# Pasa_Banda_Inferior.net
KiCad netlist of a schematic drawn in Altium Designer
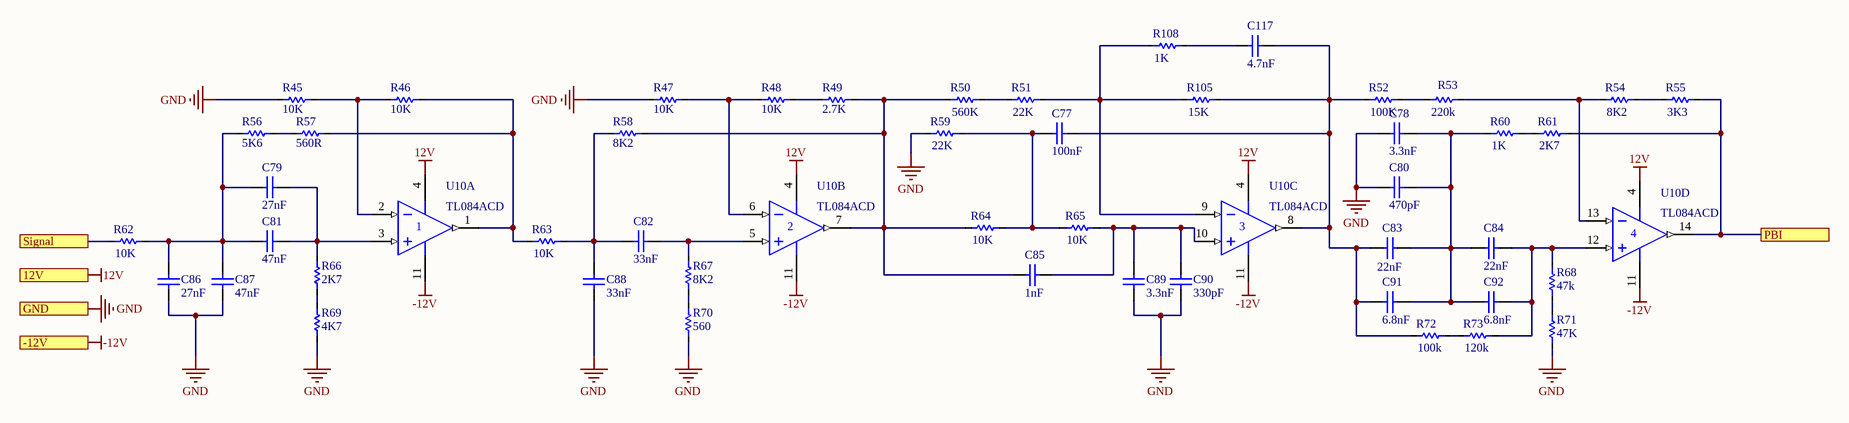
[diagram p0: Pasa Banda Inferior.SchDoc]

(export (version "E")
  (design (tool "Eeschema 10.0.6"))
  (components
    (comp (ref "C77")
      (value "Cap Ceramico Disco")
      (footprint "CAP DISCO 200mil")
      (description "Capacitor Ceramico de Insercion")
      (fields (field (name "VALOR") "100nF"))
      (libsource (lib "RUF-Dispositivos-Grales") (part "Cap Ceramico Disco"))
    )
    (comp (ref "C78")
      (value "Cap Ceramico Disco")
      (footprint "CAP DISCO 200mil")
      (description "Capacitor Ceramico de Insercion")
      (fields (field (name "VALOR") "3.3nF"))
      (libsource (lib "RUF-Dispositivos-Grales") (part "Cap Ceramico Disco"))
    )
    (comp (ref "C79")
      (value "Cap Ceramico Disco")
      (footprint "CAP DISCO 200mil")
      (description "Capacitor Ceramico de Insercion")
      (fields (field (name "VALOR") "27nF"))
      (libsource (lib "RUF-Dispositivos-Grales") (part "Cap Ceramico Disco"))
    )
    (comp (ref "C80")
      (value "Cap Ceramico Disco")
      (footprint "cap 10")
      (description "Capacitor Ceramico de Insercion")
      (fields (field (name "VALOR") "470pF"))
      (libsource (lib "RUF-Dispositivos-Grales") (part "Cap Ceramico Disco"))
    )
    (comp (ref "C81")
      (value "Cap Ceramico Disco")
      (footprint "cap 10")
      (description "Capacitor Ceramico de Insercion")
      (fields (field (name "VALOR") "47nF"))
      (libsource (lib "RUF-Dispositivos-Grales") (part "Cap Ceramico Disco"))
    )
    (comp (ref "C82")
      (value "Cap Ceramico Disco")
      (footprint "cap 10")
      (description "Capacitor Ceramico de Insercion")
      (fields (field (name "VALOR") "33nF"))
      (libsource (lib "RUF-Dispositivos-Grales") (part "Cap Ceramico Disco"))
    )
    (comp (ref "C83")
      (value "Cap Ceramico Disco")
      (footprint "cap 10")
      (description "Capacitor Ceramico de Insercion")
      (fields (field (name "VALOR") "22nF"))
      (libsource (lib "RUF-Dispositivos-Grales") (part "Cap Ceramico Disco"))
    )
    (comp (ref "C84")
      (value "Cap Ceramico Disco")
      (footprint "cap 10")
      (description "Capacitor Ceramico de Insercion")
      (fields (field (name "VALOR") "22nF"))
      (libsource (lib "RUF-Dispositivos-Grales") (part "Cap Ceramico Disco"))
    )
    (comp (ref "C85")
      (value "Cap Ceramico Disco")
      (footprint "CAP DISCO 200mil")
      (description "Capacitor Ceramico de Insercion")
      (fields (field (name "VALOR") "1nF"))
      (libsource (lib "RUF-Dispositivos-Grales") (part "Cap Ceramico Disco"))
    )
    (comp (ref "C86")
      (value "Cap Ceramico Disco")
      (footprint "CAP DISCO 200mil")
      (description "Capacitor Ceramico de Insercion")
      (fields (field (name "VALOR") "27nF"))
      (libsource (lib "RUF-Dispositivos-Grales") (part "Cap Ceramico Disco"))
    )
    (comp (ref "C87")
      (value "Cap Ceramico Disco")
      (footprint "cap 10")
      (description "Capacitor Ceramico de Insercion")
      (fields (field (name "VALOR") "47nF"))
      (libsource (lib "RUF-Dispositivos-Grales") (part "Cap Ceramico Disco"))
    )
    (comp (ref "C88")
      (value "Cap Ceramico Disco")
      (footprint "cap 10")
      (description "Capacitor Ceramico de Insercion")
      (fields (field (name "VALOR") "33nF"))
      (libsource (lib "RUF-Dispositivos-Grales") (part "Cap Ceramico Disco"))
    )
    (comp (ref "C89")
      (value "Cap Ceramico Disco")
      (footprint "CAP DISCO 200mil")
      (description "Capacitor Ceramico de Insercion")
      (fields (field (name "VALOR") "3.3nF"))
      (libsource (lib "RUF-Dispositivos-Grales") (part "Cap Ceramico Disco"))
    )
    (comp (ref "C90")
      (value "Cap Ceramico Disco")
      (footprint "CAP DISCO 150mil")
      (description "Capacitor Ceramico de Insercion")
      (fields (field (name "VALOR") "330pF"))
      (libsource (lib "RUF-Dispositivos-Grales") (part "Cap Ceramico Disco"))
    )
    (comp (ref "C91")
      (value "Cap Ceramico Disco")
      (footprint "CAP DISCO 200mil")
      (description "Capacitor Ceramico de Insercion")
      (fields (field (name "VALOR") "6.8nF"))
      (libsource (lib "RUF-Dispositivos-Grales") (part "Cap Ceramico Disco"))
    )
    (comp (ref "C92")
      (value "Cap Ceramico Disco")
      (footprint "CAP DISCO 200mil")
      (description "Capacitor Ceramico de Insercion")
      (fields (field (name "VALOR") "6.8nF"))
      (libsource (lib "RUF-Dispositivos-Grales") (part "Cap Ceramico Disco"))
    )
    (comp (ref "C117")
      (value "Cap Ceramico Disco")
      (footprint "CAP DISCO 200mil")
      (description "Capacitor Ceramico de Insercion")
      (fields (field (name "VALOR") "4.7nF"))
      (libsource (lib "RUF-Dispositivos-Grales") (part "Cap Ceramico Disco"))
    )
    (comp (ref "R45")
      (value "Res SMD")
      (footprint "1206 resistor")
      (description "Res Smd")
      (fields (field (name "VALOR") "10K"))
      (libsource (lib "RUF-Dispositivos-Grales") (part "Res SMD"))
    )
    (comp (ref "R46")
      (value "Res SMD")
      (footprint "1206 resistor")
      (description "Res Smd")
      (fields (field (name "VALOR") "10K"))
      (libsource (lib "RUF-Dispositivos-Grales") (part "Res SMD"))
    )
    (comp (ref "R47")
      (value "Res SMD")
      (footprint "1206 resistor")
      (description "Res Smd")
      (fields (field (name "VALOR") "10K"))
      (libsource (lib "RUF-Dispositivos-Grales") (part "Res SMD"))
    )
    (comp (ref "R48")
      (value "Res SMD")
      (footprint "1206 resistor")
      (description "Res Smd")
      (fields (field (name "VALOR") "10K"))
      (libsource (lib "RUF-Dispositivos-Grales") (part "Res SMD"))
    )
    (comp (ref "R49")
      (value "Res SMD")
      (footprint "1206 resistor")
      (description "Res Smd")
      (fields (field (name "VALOR") "2.7K"))
      (libsource (lib "RUF-Dispositivos-Grales") (part "Res SMD"))
    )
    (comp (ref "R50")
      (value "Res SMD")
      (footprint "RES AXIAL 400mil")
      (description "Res Smd")
      (fields (field (name "VALOR") "560K"))
      (libsource (lib "RUF-Dispositivos-Grales") (part "Res SMD"))
    )
    (comp (ref "R51")
      (value "Res SMD")
      (footprint "1206 resistor")
      (description "Res Smd")
      (fields (field (name "VALOR") "22K"))
      (libsource (lib "RUF-Dispositivos-Grales") (part "Res SMD"))
    )
    (comp (ref "R52")
      (value "Res SMD")
      (footprint "RES AXIAL 400mil")
      (description "Res Smd")
      (fields (field (name "VALOR") "100K"))
      (libsource (lib "RUF-Dispositivos-Grales") (part "Res SMD"))
    )
    (comp (ref "R53")
      (value "Res SMD")
      (footprint "RES AXIAL 400mil")
      (description "Res Smd")
      (fields (field (name "VALOR") "220k"))
      (libsource (lib "RUF-Dispositivos-Grales") (part "Res SMD"))
    )
    (comp (ref "R54")
      (value "Res SMD")
      (footprint "1206 resistor")
      (description "Res Smd")
      (fields (field (name "VALOR") "8K2"))
      (libsource (lib "RUF-Dispositivos-Grales") (part "Res SMD"))
    )
    (comp (ref "R55")
      (value "Res SMD")
      (footprint "1206 resistor")
      (description "Res Smd")
      (fields (field (name "VALOR") "3K3"))
      (libsource (lib "RUF-Dispositivos-Grales") (part "Res SMD"))
    )
    (comp (ref "R56")
      (value "Res SMD")
      (footprint "1206 resistor")
      (description "Res Smd")
      (fields (field (name "VALOR") "5K6"))
      (libsource (lib "RUF-Dispositivos-Grales") (part "Res SMD"))
    )
    (comp (ref "R57")
      (value "Res SMD")
      (footprint "1206 resistor")
      (description "Res Smd")
      (fields (field (name "VALOR") "560R"))
      (libsource (lib "RUF-Dispositivos-Grales") (part "Res SMD"))
    )
    (comp (ref "R58")
      (value "Res SMD")
      (footprint "1206 resistor")
      (description "Res Smd")
      (fields (field (name "VALOR") "8K2"))
      (libsource (lib "RUF-Dispositivos-Grales") (part "Res SMD"))
    )
    (comp (ref "R59")
      (value "Res SMD")
      (footprint "1206 resistor")
      (description "Res Smd")
      (fields (field (name "VALOR") "22K"))
      (libsource (lib "RUF-Dispositivos-Grales") (part "Res SMD"))
    )
    (comp (ref "R60")
      (value "Res SMD")
      (footprint "1206 resistor")
      (description "Res Smd")
      (fields (field (name "VALOR") "1K"))
      (libsource (lib "RUF-Dispositivos-Grales") (part "Res SMD"))
    )
    (comp (ref "R61")
      (value "Res SMD")
      (footprint "1206 resistor")
      (description "Res Smd")
      (fields (field (name "VALOR") "2K7"))
      (libsource (lib "RUF-Dispositivos-Grales") (part "Res SMD"))
    )
    (comp (ref "R62")
      (value "Res SMD")
      (footprint "1206 resistor")
      (description "Res Smd")
      (fields (field (name "VALOR") "10K"))
      (libsource (lib "RUF-Dispositivos-Grales") (part "Res SMD"))
    )
    (comp (ref "R63")
      (value "Res SMD")
      (footprint "1206 resistor")
      (description "Res Smd")
      (fields (field (name "VALOR") "10K"))
      (libsource (lib "RUF-Dispositivos-Grales") (part "Res SMD"))
    )
    (comp (ref "R64")
      (value "Res SMD")
      (footprint "1206 resistor")
      (description "Res Smd")
      (fields (field (name "VALOR") "10K"))
      (libsource (lib "RUF-Dispositivos-Grales") (part "Res SMD"))
    )
    (comp (ref "R65")
      (value "Res SMD")
      (footprint "1206 resistor")
      (description "Res Smd")
      (fields (field (name "VALOR") "10K"))
      (libsource (lib "RUF-Dispositivos-Grales") (part "Res SMD"))
    )
    (comp (ref "R66")
      (value "Res SMD")
      (footprint "1206 resistor")
      (description "Res Smd")
      (fields (field (name "VALOR") "2K7"))
      (libsource (lib "RUF-Dispositivos-Grales") (part "Res SMD"))
    )
    (comp (ref "R67")
      (value "Res SMD")
      (footprint "1206 resistor")
      (description "Res Smd")
      (fields (field (name "VALOR") "8K2"))
      (libsource (lib "RUF-Dispositivos-Grales") (part "Res SMD"))
    )
    (comp (ref "R68")
      (value "Res SMD")
      (footprint "RES AXIAL 400mil")
      (description "Res Smd")
      (fields (field (name "VALOR") "47k"))
      (libsource (lib "RUF-Dispositivos-Grales") (part "Res SMD"))
    )
    (comp (ref "R69")
      (value "Res SMD")
      (footprint "1206 resistor")
      (description "Res Smd")
      (fields (field (name "VALOR") "4K7"))
      (libsource (lib "RUF-Dispositivos-Grales") (part "Res SMD"))
    )
    (comp (ref "R70")
      (value "Res SMD")
      (footprint "1206 resistor")
      (description "Res Smd")
      (fields (field (name "VALOR") "560"))
      (libsource (lib "RUF-Dispositivos-Grales") (part "Res SMD"))
    )
    (comp (ref "R71")
      (value "Res SMD")
      (footprint "RES AXIAL 400mil")
      (description "Res Smd")
      (fields (field (name "VALOR") "47K"))
      (libsource (lib "RUF-Dispositivos-Grales") (part "Res SMD"))
    )
    (comp (ref "R72")
      (value "Res SMD")
      (footprint "RES AXIAL 400mil")
      (description "Res Smd")
      (fields (field (name "VALOR") "100k"))
      (libsource (lib "RUF-Dispositivos-Grales") (part "Res SMD"))
    )
    (comp (ref "R73")
      (value "Res SMD")
      (footprint "RES AXIAL 400mil")
      (description "Res Smd")
      (fields (field (name "VALOR") "120k"))
      (libsource (lib "RUF-Dispositivos-Grales") (part "Res SMD"))
    )
    (comp (ref "R105")
      (value "Res SMD")
      (footprint "1206 resistor")
      (description "Res Smd")
      (fields (field (name "VALOR") "15K"))
      (libsource (lib "RUF-Dispositivos-Grales") (part "Res SMD"))
    )
    (comp (ref "R108")
      (value "Res SMD")
      (footprint "1206 resistor")
      (description "Res Smd")
      (fields (field (name "VALOR") "1K"))
      (libsource (lib "RUF-Dispositivos-Grales") (part "Res SMD"))
    )
    (comp (ref "U10")
      (value "TL084ACD")
      (footprint "751A-02_N")
      (description "JFET-Input Operational Amplifier")
      (fields (field (name "PUBLISHER") "Altium Limited"))
      (libsource (lib "Motorola Amplifier Operational Amplifier") (part "TL084ACD"))
    )
  )
  (nets
    (net (code "1") (name "-12V") (class "Default")
      (node (ref "U10") (pin "11") (pinfunction "V-_11") (pintype "power_in"))
    )
    (net (code "2") (name "/PBI") (class "Default")
      (node (ref "R55") (pin "2") (pinfunction "2_2") (pintype "passive"))
      (node (ref "R61") (pin "2") (pinfunction "2_2") (pintype "passive"))
      (node (ref "U10") (pin "14") (pinfunction "OUT_14") (pintype "output"))
    )
    (net (code "3") (name "/Signal") (class "Default")
      (node (ref "R62") (pin "1") (pinfunction "1_1") (pintype "passive"))
    )
    (net (code "4") (name "12V") (class "Default")
      (node (ref "U10") (pin "4") (pinfunction "V+_4") (pintype "power_in"))
    )
    (net (code "5") (name "GND") (class "Default")
      (node (ref "C78") (pin "2") (pinfunction "2_2") (pintype "passive"))
      (node (ref "C80") (pin "2") (pinfunction "2_2") (pintype "passive"))
      (node (ref "C86") (pin "1") (pinfunction "1_1") (pintype "passive"))
      (node (ref "C87") (pin "1") (pinfunction "1_1") (pintype "passive"))
      (node (ref "C88") (pin "1") (pinfunction "1_1") (pintype "passive"))
      (node (ref "C89") (pin "2") (pinfunction "2_2") (pintype "passive"))
      (node (ref "C90") (pin "2") (pinfunction "2_2") (pintype "passive"))
      (node (ref "R45") (pin "2") (pinfunction "2_2") (pintype "passive"))
      (node (ref "R47") (pin "2") (pinfunction "2_2") (pintype "passive"))
      (node (ref "R59") (pin "1") (pinfunction "1_1") (pintype "passive"))
      (node (ref "R69") (pin "1") (pinfunction "1_1") (pintype "passive"))
      (node (ref "R70") (pin "1") (pinfunction "1_1") (pintype "passive"))
      (node (ref "R71") (pin "1") (pinfunction "1_1") (pintype "passive"))
    )
    (net (code "6") (name "Net-(C77-Pad2)") (class "Default")
      (node (ref "C77") (pin "2") (pinfunction "2_2") (pintype "passive"))
      (node (ref "R59") (pin "2") (pinfunction "2_2") (pintype "passive"))
      (node (ref "R64") (pin "2") (pinfunction "2_2") (pintype "passive"))
      (node (ref "R65") (pin "1") (pinfunction "1_1") (pintype "passive"))
    )
    (net (code "7") (name "Net-(C78-Pad1)") (class "Default")
      (node (ref "C78") (pin "1") (pinfunction "1_1") (pintype "passive"))
      (node (ref "C80") (pin "1") (pinfunction "1_1") (pintype "passive"))
      (node (ref "C83") (pin "1") (pinfunction "1_1") (pintype "passive"))
      (node (ref "C84") (pin "2") (pinfunction "2_2") (pintype "passive"))
      (node (ref "C91") (pin "1") (pinfunction "1_1") (pintype "passive"))
      (node (ref "C92") (pin "2") (pinfunction "2_2") (pintype "passive"))
      (node (ref "R60") (pin "1") (pinfunction "1_1") (pintype "passive"))
    )
    (net (code "8") (name "Net-(C79-Pad2)") (class "Default")
      (node (ref "C79") (pin "2") (pinfunction "2_2") (pintype "passive"))
      (node (ref "C81") (pin "2") (pinfunction "2_2") (pintype "passive"))
      (node (ref "C86") (pin "2") (pinfunction "2_2") (pintype "passive"))
      (node (ref "C87") (pin "2") (pinfunction "2_2") (pintype "passive"))
      (node (ref "R56") (pin "2") (pinfunction "2_2") (pintype "passive"))
      (node (ref "R62") (pin "2") (pinfunction "2_2") (pintype "passive"))
    )
    (net (code "9") (name "Net-(C82-Pad2)") (class "Default")
      (node (ref "C82") (pin "2") (pinfunction "2_2") (pintype "passive"))
      (node (ref "C88") (pin "2") (pinfunction "2_2") (pintype "passive"))
      (node (ref "R58") (pin "2") (pinfunction "2_2") (pintype "passive"))
      (node (ref "R63") (pin "2") (pinfunction "2_2") (pintype "passive"))
    )
    (net (code "10") (name "Net-(C117-Pad2)") (class "Default")
      (node (ref "C117") (pin "2") (pinfunction "2_2") (pintype "passive"))
      (node (ref "R108") (pin "2") (pinfunction "2_2") (pintype "passive"))
    )
    (net (code "11") (name "Net-(R48-Pad1)") (class "Default")
      (node (ref "R48") (pin "1") (pinfunction "1_1") (pintype "passive"))
      (node (ref "R49") (pin "2") (pinfunction "2_2") (pintype "passive"))
    )
    (net (code "12") (name "Net-(R50-Pad2)") (class "Default")
      (node (ref "R50") (pin "2") (pinfunction "2_2") (pintype "passive"))
      (node (ref "R51") (pin "1") (pinfunction "1_1") (pintype "passive"))
    )
    (net (code "13") (name "Net-(R52-Pad2)") (class "Default")
      (node (ref "R52") (pin "2") (pinfunction "2_2") (pintype "passive"))
      (node (ref "R53") (pin "1") (pinfunction "1_1") (pintype "passive"))
    )
    (net (code "14") (name "Net-(R54-Pad2)") (class "Default")
      (node (ref "R54") (pin "2") (pinfunction "2_2") (pintype "passive"))
      (node (ref "R55") (pin "1") (pinfunction "1_1") (pintype "passive"))
    )
    (net (code "15") (name "Net-(R56-Pad1)") (class "Default")
      (node (ref "R56") (pin "1") (pinfunction "1_1") (pintype "passive"))
      (node (ref "R57") (pin "2") (pinfunction "2_2") (pintype "passive"))
    )
    (net (code "16") (name "Net-(R60-Pad2)") (class "Default")
      (node (ref "R60") (pin "2") (pinfunction "2_2") (pintype "passive"))
      (node (ref "R61") (pin "1") (pinfunction "1_1") (pintype "passive"))
    )
    (net (code "17") (name "Net-(R66-Pad1)") (class "Default")
      (node (ref "R66") (pin "1") (pinfunction "1_1") (pintype "passive"))
      (node (ref "R69") (pin "2") (pinfunction "2_2") (pintype "passive"))
    )
    (net (code "18") (name "Net-(R67-Pad1)") (class "Default")
      (node (ref "R67") (pin "1") (pinfunction "1_1") (pintype "passive"))
      (node (ref "R70") (pin "2") (pinfunction "2_2") (pintype "passive"))
    )
    (net (code "19") (name "Net-(R68-Pad1)") (class "Default")
      (node (ref "R68") (pin "1") (pinfunction "1_1") (pintype "passive"))
      (node (ref "R71") (pin "2") (pinfunction "2_2") (pintype "passive"))
    )
    (net (code "20") (name "Net-(R72-Pad2)") (class "Default")
      (node (ref "R72") (pin "2") (pinfunction "2_2") (pintype "passive"))
      (node (ref "R73") (pin "1") (pinfunction "1_1") (pintype "passive"))
    )
    (net (code "21") (name "Net-(U10A-IN+)") (class "Default")
      (node (ref "C79") (pin "1") (pinfunction "1_1") (pintype "passive"))
      (node (ref "C81") (pin "1") (pinfunction "1_1") (pintype "passive"))
      (node (ref "R66") (pin "2") (pinfunction "2_2") (pintype "passive"))
      (node (ref "U10") (pin "3") (pinfunction "IN+_3") (pintype "input"))
    )
    (net (code "22") (name "Net-(U10A-IN-)") (class "Default")
      (node (ref "R45") (pin "1") (pinfunction "1_1") (pintype "passive"))
      (node (ref "R46") (pin "2") (pinfunction "2_2") (pintype "passive"))
      (node (ref "U10") (pin "2") (pinfunction "IN-_2") (pintype "input"))
    )
    (net (code "23") (name "Net-(U10A-OUT)") (class "Default")
      (node (ref "R46") (pin "1") (pinfunction "1_1") (pintype "passive"))
      (node (ref "R57") (pin "1") (pinfunction "1_1") (pintype "passive"))
      (node (ref "R63") (pin "1") (pinfunction "1_1") (pintype "passive"))
      (node (ref "U10") (pin "1") (pinfunction "OUT_1") (pintype "output"))
    )
    (net (code "24") (name "Net-(U10B-IN+)") (class "Default")
      (node (ref "C82") (pin "1") (pinfunction "1_1") (pintype "passive"))
      (node (ref "R67") (pin "2") (pinfunction "2_2") (pintype "passive"))
      (node (ref "U10") (pin "5") (pinfunction "IN+_5") (pintype "input"))
    )
    (net (code "25") (name "Net-(U10B-IN-)") (class "Default")
      (node (ref "R47") (pin "1") (pinfunction "1_1") (pintype "passive"))
      (node (ref "R48") (pin "2") (pinfunction "2_2") (pintype "passive"))
      (node (ref "U10") (pin "6") (pinfunction "IN-_6") (pintype "input"))
    )
    (net (code "26") (name "Net-(U10B-OUT)") (class "Default")
      (node (ref "C85") (pin "2") (pinfunction "2_2") (pintype "passive"))
      (node (ref "R49") (pin "1") (pinfunction "1_1") (pintype "passive"))
      (node (ref "R50") (pin "1") (pinfunction "1_1") (pintype "passive"))
      (node (ref "R58") (pin "1") (pinfunction "1_1") (pintype "passive"))
      (node (ref "R64") (pin "1") (pinfunction "1_1") (pintype "passive"))
      (node (ref "U10") (pin "7") (pinfunction "OUT_7") (pintype "output"))
    )
    (net (code "27") (name "Net-(U10C-IN+)") (class "Default")
      (node (ref "C85") (pin "1") (pinfunction "1_1") (pintype "passive"))
      (node (ref "C89") (pin "1") (pinfunction "1_1") (pintype "passive"))
      (node (ref "C90") (pin "1") (pinfunction "1_1") (pintype "passive"))
      (node (ref "R65") (pin "2") (pinfunction "2_2") (pintype "passive"))
      (node (ref "U10") (pin "10") (pinfunction "IN+_10") (pintype "input"))
    )
    (net (code "28") (name "Net-(U10C-IN-)") (class "Default")
      (node (ref "R105") (pin "1") (pinfunction "1_1") (pintype "passive"))
      (node (ref "R108") (pin "1") (pinfunction "1_1") (pintype "passive"))
      (node (ref "R51") (pin "2") (pinfunction "2_2") (pintype "passive"))
      (node (ref "U10") (pin "9") (pinfunction "IN-_9") (pintype "input"))
    )
    (net (code "29") (name "Net-(U10C-OUT)") (class "Default")
      (node (ref "C117") (pin "1") (pinfunction "1_1") (pintype "passive"))
      (node (ref "C77") (pin "1") (pinfunction "1_1") (pintype "passive"))
      (node (ref "C83") (pin "2") (pinfunction "2_2") (pintype "passive"))
      (node (ref "C91") (pin "2") (pinfunction "2_2") (pintype "passive"))
      (node (ref "R105") (pin "2") (pinfunction "2_2") (pintype "passive"))
      (node (ref "R52") (pin "1") (pinfunction "1_1") (pintype "passive"))
      (node (ref "R72") (pin "1") (pinfunction "1_1") (pintype "passive"))
      (node (ref "U10") (pin "8") (pinfunction "OUT_8") (pintype "output"))
    )
    (net (code "30") (name "Net-(U10D-IN+)") (class "Default")
      (node (ref "C84") (pin "1") (pinfunction "1_1") (pintype "passive"))
      (node (ref "C92") (pin "1") (pinfunction "1_1") (pintype "passive"))
      (node (ref "R68") (pin "2") (pinfunction "2_2") (pintype "passive"))
      (node (ref "R73") (pin "2") (pinfunction "2_2") (pintype "passive"))
      (node (ref "U10") (pin "12") (pinfunction "IN+_12") (pintype "input"))
    )
    (net (code "31") (name "Net-(U10D-IN-)") (class "Default")
      (node (ref "R53") (pin "2") (pinfunction "2_2") (pintype "passive"))
      (node (ref "R54") (pin "1") (pinfunction "1_1") (pintype "passive"))
      (node (ref "U10") (pin "13") (pinfunction "IN-_13") (pintype "input"))
    )
  )
)
